# Shield_2_No_Ardy.net
KiCad netlist of a schematic drawn in EAGLE
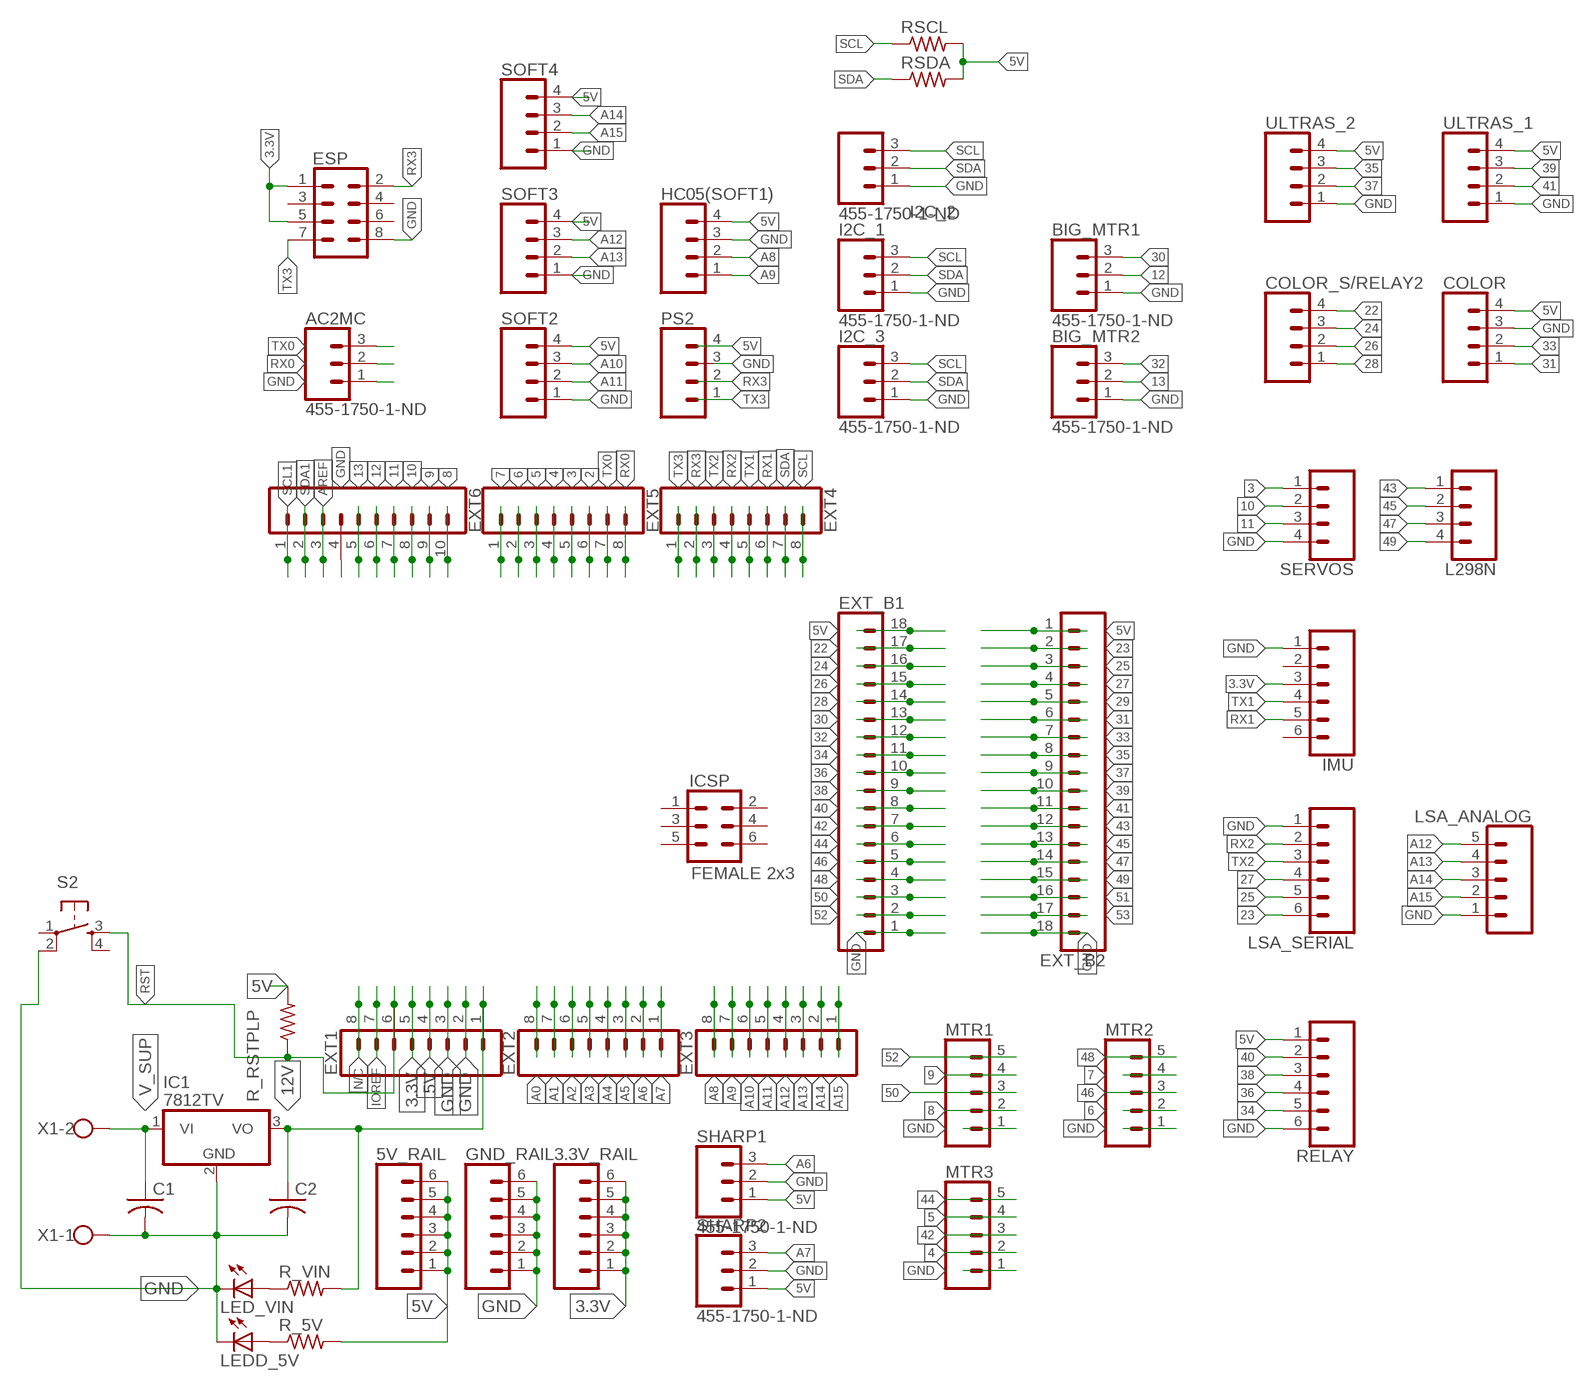
[diagram p0: schematic, sheet 1]

(export (version "E")
  (design (tool "Eeschema 10.0.6"))
  (components
    (comp (ref "3.3V_RAIL")
      (value "CONN_06SILK_FEMALE_PTH")
      (footprint "eagle-import:1X06")
      (libsource (lib "eagle-import") (part "CONN_06SILK_FEMALE_PTH"))
    )
    (comp (ref "5V_RAIL")
      (value "CONN_06SILK_FEMALE_PTH")
      (footprint "eagle-import:1X06")
      (libsource (lib "eagle-import") (part "CONN_06SILK_FEMALE_PTH"))
    )
    (comp (ref "AC2MC")
      (value "455-1750-1-ND")
      (footprint "eagle-import:1X03")
      (libsource (lib "eagle-import") (part "CONN_03"))
    )
    (comp (ref "BIG_MTR1")
      (value "455-1750-1-ND")
      (footprint "eagle-import:1X03")
      (libsource (lib "eagle-import") (part "CONN_03"))
    )
    (comp (ref "BIG_MTR2")
      (value "455-1750-1-ND")
      (footprint "eagle-import:1X03")
      (libsource (lib "eagle-import") (part "CONN_03"))
    )
    (comp (ref "C1")
      (value "C-US025-024X044")
      (footprint "eagle-import:C025-024X044")
      (libsource (lib "eagle-import") (part "C-US025-024X044"))
    )
    (comp (ref "C2")
      (value "C-US025-024X044")
      (footprint "eagle-import:C025-024X044")
      (libsource (lib "eagle-import") (part "C-US025-024X044"))
    )
    (comp (ref "COLOR")
      (value "CONN_04")
      (footprint "eagle-import:1X04")
      (libsource (lib "eagle-import") (part "CONN_04"))
    )
    (comp (ref "COLOR_S/RELAY2")
      (value "CONN_04")
      (footprint "eagle-import:1X04")
      (libsource (lib "eagle-import") (part "CONN_04"))
    )
    (comp (ref "ESP")
      (value "CONN_04X2")
      (footprint "eagle-import:2X4")
      (libsource (lib "eagle-import") (part "CONN_04X2"))
    )
    (comp (ref "EXT1")
      (value "CONN_08\"")
      (footprint "eagle-import:1X08")
      (libsource (lib "eagle-import") (part "CONN_08{dblquote}"))
    )
    (comp (ref "EXT2")
      (value "CONN_08\"")
      (footprint "eagle-import:1X08")
      (libsource (lib "eagle-import") (part "CONN_08{dblquote}"))
    )
    (comp (ref "EXT3")
      (value "CONN_08\"")
      (footprint "eagle-import:1X08")
      (libsource (lib "eagle-import") (part "CONN_08{dblquote}"))
    )
    (comp (ref "EXT4")
      (value "CONN_08\"")
      (footprint "eagle-import:1X08")
      (libsource (lib "eagle-import") (part "CONN_08{dblquote}"))
    )
    (comp (ref "EXT5")
      (value "CONN_08\"")
      (footprint "eagle-import:1X08")
      (libsource (lib "eagle-import") (part "CONN_08{dblquote}"))
    )
    (comp (ref "EXT6")
      (value "CONN_10\"")
      (footprint "eagle-import:1X10")
      (libsource (lib "eagle-import") (part "CONN_10{dblquote}"))
    )
    (comp (ref "EXT_B1")
      (value "CONN_18")
      (footprint "eagle-import:1X18_NO_SILK")
      (libsource (lib "eagle-import") (part "CONN_18"))
    )
    (comp (ref "EXT_B2")
      (value "CONN_18")
      (footprint "eagle-import:1X18_NO_SILK")
      (libsource (lib "eagle-import") (part "CONN_18"))
    )
    (comp (ref "GND_RAIL")
      (value "CONN_06SILK_FEMALE_PTH")
      (footprint "eagle-import:1X06")
      (libsource (lib "eagle-import") (part "CONN_06SILK_FEMALE_PTH"))
    )
    (comp (ref "HC05(SOFT1)")
      (value "CONN_04")
      (footprint "eagle-import:1X04")
      (libsource (lib "eagle-import") (part "CONN_04"))
    )
    (comp (ref "I2C_1")
      (value "455-1750-1-ND")
      (footprint "eagle-import:1X03")
      (libsource (lib "eagle-import") (part "CONN_03"))
    )
    (comp (ref "I2C_2")
      (value "455-1750-1-ND")
      (footprint "eagle-import:1X03")
      (libsource (lib "eagle-import") (part "CONN_03"))
    )
    (comp (ref "I2C_3")
      (value "455-1750-1-ND")
      (footprint "eagle-import:1X03")
      (libsource (lib "eagle-import") (part "CONN_03"))
    )
    (comp (ref "IC1")
      (value "7812TV")
      (footprint "eagle-import:TO220V")
      (libsource (lib "eagle-import") (part "78TV12"))
    )
    (comp (ref "ICSP")
      (value "FEMALE 2x3")
      (footprint "eagle-import:2X3")
      (libsource (lib "eagle-import") (part "CONN_03X2FEMALE"))
    )
    (comp (ref "IMU")
      (value "CONN_06SILK_FEMALE_PTH")
      (footprint "eagle-import:1X06")
      (libsource (lib "eagle-import") (part "CONN_06SILK_FEMALE_PTH"))
    )
    (comp (ref "L298N")
      (value "CONN_04")
      (footprint "eagle-import:1X04")
      (libsource (lib "eagle-import") (part "CONN_04"))
    )
    (comp (ref "LEDD_5V")
      (value "LED5MM")
      (footprint "eagle-import:LED5MM")
      (libsource (lib "eagle-import") (part "LED5MM"))
    )
    (comp (ref "LED_VIN")
      (value "LED5MM")
      (footprint "eagle-import:LED5MM")
      (libsource (lib "eagle-import") (part "LED5MM"))
    )
    (comp (ref "LSA_ANALOG")
      (value "CONN_05")
      (footprint "eagle-import:1X05")
      (libsource (lib "eagle-import") (part "CONN_05"))
    )
    (comp (ref "LSA_SERIAL")
      (value "CONN_06SILK_FEMALE_PTH")
      (footprint "eagle-import:1X06")
      (libsource (lib "eagle-import") (part "CONN_06SILK_FEMALE_PTH"))
    )
    (comp (ref "MTR1")
      (value "CONN_05")
      (footprint "eagle-import:1X05")
      (libsource (lib "eagle-import") (part "CONN_05"))
    )
    (comp (ref "MTR2")
      (value "CONN_05")
      (footprint "eagle-import:1X05")
      (libsource (lib "eagle-import") (part "CONN_05"))
    )
    (comp (ref "MTR3")
      (value "CONN_05")
      (footprint "eagle-import:1X05")
      (libsource (lib "eagle-import") (part "CONN_05"))
    )
    (comp (ref "PS2")
      (value "CONN_04")
      (footprint "eagle-import:1X04")
      (libsource (lib "eagle-import") (part "CONN_04"))
    )
    (comp (ref "RELAY")
      (value "CONN_06SILK_FEMALE_PTH")
      (footprint "eagle-import:1X06")
      (libsource (lib "eagle-import") (part "CONN_06SILK_FEMALE_PTH"))
    )
    (comp (ref "RSCL")
      (value "R-US_0204/7")
      (footprint "eagle-import:0204_7")
      (libsource (lib "eagle-import") (part "R-US_0204/7"))
    )
    (comp (ref "RSDA")
      (value "R-US_0204/7")
      (footprint "eagle-import:0204_7")
      (libsource (lib "eagle-import") (part "R-US_0204/7"))
    )
    (comp (ref "R_5V")
      (value "R-US_0204/7")
      (footprint "eagle-import:0204_7")
      (libsource (lib "eagle-import") (part "R-US_0204/7"))
    )
    (comp (ref "R_RSTPLP")
      (value "R-US_0204/7")
      (footprint "eagle-import:0204_7")
      (libsource (lib "eagle-import") (part "R-US_0204/7"))
    )
    (comp (ref "R_VIN")
      (value "R-US_0204/7")
      (footprint "eagle-import:0204_7")
      (libsource (lib "eagle-import") (part "R-US_0204/7"))
    )
    (comp (ref "S2")
      (value "TAC_SWITCHPTH")
      (footprint "eagle-import:TACTILE-PTH")
      (libsource (lib "eagle-import") (part "TAC_SWITCHPTH"))
    )
    (comp (ref "SERVOS")
      (value "CONN_04")
      (footprint "eagle-import:1X04")
      (libsource (lib "eagle-import") (part "CONN_04"))
    )
    (comp (ref "SHARP1")
      (value "455-1750-1-ND")
      (footprint "eagle-import:1X03")
      (libsource (lib "eagle-import") (part "CONN_03"))
    )
    (comp (ref "SHARP2")
      (value "455-1750-1-ND")
      (footprint "eagle-import:1X03")
      (libsource (lib "eagle-import") (part "CONN_03"))
    )
    (comp (ref "SOFT2")
      (value "CONN_04")
      (footprint "eagle-import:1X04")
      (libsource (lib "eagle-import") (part "CONN_04"))
    )
    (comp (ref "SOFT3")
      (value "CONN_04")
      (footprint "eagle-import:1X04")
      (libsource (lib "eagle-import") (part "CONN_04"))
    )
    (comp (ref "SOFT4")
      (value "CONN_04")
      (footprint "eagle-import:1X04")
      (libsource (lib "eagle-import") (part "CONN_04"))
    )
    (comp (ref "ULTRAS_1")
      (value "CONN_04")
      (footprint "eagle-import:1X04")
      (libsource (lib "eagle-import") (part "CONN_04"))
    )
    (comp (ref "ULTRAS_2")
      (value "CONN_04")
      (footprint "eagle-import:1X04")
      (libsource (lib "eagle-import") (part "CONN_04"))
    )
    (comp (ref "X1")
      (value "W237-102")
      (footprint "eagle-import:W237-102")
      (fields (field (name "MPN") "237-102"))
      (libsource (lib "eagle-import") (part "W237-102"))
    )
  )
  (nets
    (net (code "1") (name "2") (class "Default")
      (node (ref "EXT5") (pin "6") (pinfunction "6_6") (pintype "passive"))
    )
    (net (code "2") (name "3") (class "Default")
      (node (ref "EXT5") (pin "5") (pinfunction "5_5") (pintype "passive"))
      (node (ref "SERVOS") (pin "1") (pinfunction "1_1") (pintype "passive"))
    )
    (net (code "3") (name "3.3V") (class "Default")
      (node (ref "3.3V_RAIL") (pin "1") (pinfunction "1_1") (pintype "passive"))
      (node (ref "3.3V_RAIL") (pin "2") (pinfunction "2_2") (pintype "passive"))
      (node (ref "3.3V_RAIL") (pin "3") (pinfunction "3_3") (pintype "passive"))
      (node (ref "3.3V_RAIL") (pin "4") (pinfunction "4_4") (pintype "passive"))
      (node (ref "3.3V_RAIL") (pin "5") (pinfunction "5_5") (pintype "passive"))
      (node (ref "3.3V_RAIL") (pin "6") (pinfunction "6_6") (pintype "passive"))
      (node (ref "ESP") (pin "1") (pinfunction "1_1") (pintype "passive"))
      (node (ref "ESP") (pin "5") (pinfunction "5_5") (pintype "passive"))
      (node (ref "EXT1") (pin "5") (pinfunction "5_5") (pintype "passive"))
      (node (ref "IMU") (pin "3") (pinfunction "3_3") (pintype "passive"))
    )
    (net (code "4") (name "4") (class "Default")
      (node (ref "EXT5") (pin "4") (pinfunction "4_4") (pintype "passive"))
      (node (ref "MTR3") (pin "2") (pinfunction "2_2") (pintype "passive"))
    )
    (net (code "5") (name "5") (class "Default")
      (node (ref "EXT5") (pin "3") (pinfunction "3_3") (pintype "passive"))
      (node (ref "MTR3") (pin "4") (pinfunction "4_4") (pintype "passive"))
    )
    (net (code "6") (name "5V") (class "Default")
      (node (ref "5V_RAIL") (pin "1") (pinfunction "1_1") (pintype "passive"))
      (node (ref "5V_RAIL") (pin "2") (pinfunction "2_2") (pintype "passive"))
      (node (ref "5V_RAIL") (pin "3") (pinfunction "3_3") (pintype "passive"))
      (node (ref "5V_RAIL") (pin "4") (pinfunction "4_4") (pintype "passive"))
      (node (ref "5V_RAIL") (pin "5") (pinfunction "5_5") (pintype "passive"))
      (node (ref "5V_RAIL") (pin "6") (pinfunction "6_6") (pintype "passive"))
      (node (ref "COLOR") (pin "4") (pinfunction "4_4") (pintype "passive"))
      (node (ref "EXT1") (pin "4") (pinfunction "4_4") (pintype "passive"))
      (node (ref "EXT_B1") (pin "18") (pinfunction "18_18") (pintype "passive"))
      (node (ref "EXT_B2") (pin "1") (pinfunction "1_1") (pintype "passive"))
      (node (ref "HC05(SOFT1)") (pin "4") (pinfunction "4_4") (pintype "passive"))
      (node (ref "PS2") (pin "4") (pinfunction "4_4") (pintype "passive"))
      (node (ref "RELAY") (pin "1") (pinfunction "1_1") (pintype "passive"))
      (node (ref "RSCL") (pin "2") (pinfunction "2_2") (pintype "passive"))
      (node (ref "RSDA") (pin "2") (pinfunction "2_2") (pintype "passive"))
      (node (ref "R_5V") (pin "2") (pinfunction "2_2") (pintype "passive"))
      (node (ref "R_RSTPLP") (pin "2") (pinfunction "2_2") (pintype "passive"))
      (node (ref "SHARP1") (pin "1") (pinfunction "1_1") (pintype "passive"))
      (node (ref "SHARP2") (pin "1") (pinfunction "1_1") (pintype "passive"))
      (node (ref "SOFT2") (pin "4") (pinfunction "4_4") (pintype "passive"))
      (node (ref "SOFT3") (pin "4") (pinfunction "4_4") (pintype "passive"))
      (node (ref "SOFT4") (pin "4") (pinfunction "4_4") (pintype "passive"))
      (node (ref "ULTRAS_1") (pin "4") (pinfunction "4_4") (pintype "passive"))
      (node (ref "ULTRAS_2") (pin "4") (pinfunction "4_4") (pintype "passive"))
    )
    (net (code "7") (name "6") (class "Default")
      (node (ref "EXT5") (pin "2") (pinfunction "2_2") (pintype "passive"))
      (node (ref "MTR2") (pin "2") (pinfunction "2_2") (pintype "passive"))
    )
    (net (code "8") (name "7") (class "Default")
      (node (ref "EXT5") (pin "1") (pinfunction "1_1") (pintype "passive"))
      (node (ref "MTR2") (pin "4") (pinfunction "4_4") (pintype "passive"))
    )
    (net (code "9") (name "8") (class "Default")
      (node (ref "EXT6") (pin "10") (pinfunction "10_10") (pintype "passive"))
      (node (ref "MTR1") (pin "2") (pinfunction "2_2") (pintype "passive"))
    )
    (net (code "10") (name "9") (class "Default")
      (node (ref "EXT6") (pin "9") (pinfunction "9_9") (pintype "passive"))
      (node (ref "MTR1") (pin "4") (pinfunction "4_4") (pintype "passive"))
    )
    (net (code "11") (name "10") (class "Default")
      (node (ref "EXT6") (pin "8") (pinfunction "8_8") (pintype "passive"))
      (node (ref "SERVOS") (pin "2") (pinfunction "2_2") (pintype "passive"))
    )
    (net (code "12") (name "11") (class "Default")
      (node (ref "EXT6") (pin "7") (pinfunction "7_7") (pintype "passive"))
      (node (ref "SERVOS") (pin "3") (pinfunction "3_3") (pintype "passive"))
    )
    (net (code "13") (name "12") (class "Default")
      (node (ref "BIG_MTR1") (pin "2") (pinfunction "2_2") (pintype "passive"))
      (node (ref "EXT6") (pin "6") (pinfunction "6_6") (pintype "passive"))
    )
    (net (code "14") (name "12V") (class "Default")
      (node (ref "C2") (pin "1") (pinfunction "1_1") (pintype "passive"))
      (node (ref "EXT1") (pin "1") (pinfunction "1_1") (pintype "passive"))
      (node (ref "IC1") (pin "3") (pinfunction "VO_3") (pintype "passive"))
      (node (ref "R_VIN") (pin "2") (pinfunction "2_2") (pintype "passive"))
    )
    (net (code "15") (name "13") (class "Default")
      (node (ref "BIG_MTR2") (pin "2") (pinfunction "2_2") (pintype "passive"))
      (node (ref "EXT6") (pin "5") (pinfunction "5_5") (pintype "passive"))
    )
    (net (code "16") (name "22") (class "Default")
      (node (ref "COLOR_S/RELAY2") (pin "4") (pinfunction "4_4") (pintype "passive"))
      (node (ref "EXT_B1") (pin "17") (pinfunction "17_17") (pintype "passive"))
    )
    (net (code "17") (name "23") (class "Default")
      (node (ref "EXT_B2") (pin "2") (pinfunction "2_2") (pintype "passive"))
      (node (ref "LSA_SERIAL") (pin "6") (pinfunction "6_6") (pintype "passive"))
    )
    (net (code "18") (name "24") (class "Default")
      (node (ref "COLOR_S/RELAY2") (pin "3") (pinfunction "3_3") (pintype "passive"))
      (node (ref "EXT_B1") (pin "16") (pinfunction "16_16") (pintype "passive"))
    )
    (net (code "19") (name "25") (class "Default")
      (node (ref "EXT_B2") (pin "3") (pinfunction "3_3") (pintype "passive"))
      (node (ref "LSA_SERIAL") (pin "5") (pinfunction "5_5") (pintype "passive"))
    )
    (net (code "20") (name "26") (class "Default")
      (node (ref "COLOR_S/RELAY2") (pin "2") (pinfunction "2_2") (pintype "passive"))
      (node (ref "EXT_B1") (pin "15") (pinfunction "15_15") (pintype "passive"))
    )
    (net (code "21") (name "27") (class "Default")
      (node (ref "EXT_B2") (pin "4") (pinfunction "4_4") (pintype "passive"))
      (node (ref "LSA_SERIAL") (pin "4") (pinfunction "4_4") (pintype "passive"))
    )
    (net (code "22") (name "28") (class "Default")
      (node (ref "COLOR_S/RELAY2") (pin "1") (pinfunction "1_1") (pintype "passive"))
      (node (ref "EXT_B1") (pin "14") (pinfunction "14_14") (pintype "passive"))
    )
    (net (code "23") (name "29") (class "Default")
      (node (ref "EXT_B2") (pin "5") (pinfunction "5_5") (pintype "passive"))
    )
    (net (code "24") (name "30") (class "Default")
      (node (ref "BIG_MTR1") (pin "3") (pinfunction "3_3") (pintype "passive"))
      (node (ref "EXT_B1") (pin "13") (pinfunction "13_13") (pintype "passive"))
    )
    (net (code "25") (name "31") (class "Default")
      (node (ref "COLOR") (pin "1") (pinfunction "1_1") (pintype "passive"))
      (node (ref "EXT_B2") (pin "6") (pinfunction "6_6") (pintype "passive"))
    )
    (net (code "26") (name "32") (class "Default")
      (node (ref "BIG_MTR2") (pin "3") (pinfunction "3_3") (pintype "passive"))
      (node (ref "EXT_B1") (pin "12") (pinfunction "12_12") (pintype "passive"))
    )
    (net (code "27") (name "33") (class "Default")
      (node (ref "COLOR") (pin "2") (pinfunction "2_2") (pintype "passive"))
      (node (ref "EXT_B2") (pin "7") (pinfunction "7_7") (pintype "passive"))
    )
    (net (code "28") (name "34") (class "Default")
      (node (ref "EXT_B1") (pin "11") (pinfunction "11_11") (pintype "passive"))
      (node (ref "RELAY") (pin "5") (pinfunction "5_5") (pintype "passive"))
    )
    (net (code "29") (name "35") (class "Default")
      (node (ref "EXT_B2") (pin "8") (pinfunction "8_8") (pintype "passive"))
      (node (ref "ULTRAS_2") (pin "3") (pinfunction "3_3") (pintype "passive"))
    )
    (net (code "30") (name "36") (class "Default")
      (node (ref "EXT_B1") (pin "10") (pinfunction "10_10") (pintype "passive"))
      (node (ref "RELAY") (pin "4") (pinfunction "4_4") (pintype "passive"))
    )
    (net (code "31") (name "37") (class "Default")
      (node (ref "EXT_B2") (pin "9") (pinfunction "9_9") (pintype "passive"))
      (node (ref "ULTRAS_2") (pin "2") (pinfunction "2_2") (pintype "passive"))
    )
    (net (code "32") (name "38") (class "Default")
      (node (ref "EXT_B1") (pin "9") (pinfunction "9_9") (pintype "passive"))
      (node (ref "RELAY") (pin "3") (pinfunction "3_3") (pintype "passive"))
    )
    (net (code "33") (name "39") (class "Default")
      (node (ref "EXT_B2") (pin "10") (pinfunction "10_10") (pintype "passive"))
      (node (ref "ULTRAS_1") (pin "3") (pinfunction "3_3") (pintype "passive"))
    )
    (net (code "34") (name "40") (class "Default")
      (node (ref "EXT_B1") (pin "8") (pinfunction "8_8") (pintype "passive"))
      (node (ref "RELAY") (pin "2") (pinfunction "2_2") (pintype "passive"))
    )
    (net (code "35") (name "41") (class "Default")
      (node (ref "EXT_B2") (pin "11") (pinfunction "11_11") (pintype "passive"))
      (node (ref "ULTRAS_1") (pin "2") (pinfunction "2_2") (pintype "passive"))
    )
    (net (code "36") (name "42") (class "Default")
      (node (ref "EXT_B1") (pin "7") (pinfunction "7_7") (pintype "passive"))
      (node (ref "MTR3") (pin "3") (pinfunction "3_3") (pintype "passive"))
    )
    (net (code "37") (name "43") (class "Default")
      (node (ref "EXT_B2") (pin "12") (pinfunction "12_12") (pintype "passive"))
      (node (ref "L298N") (pin "1") (pinfunction "1_1") (pintype "passive"))
    )
    (net (code "38") (name "44") (class "Default")
      (node (ref "EXT_B1") (pin "6") (pinfunction "6_6") (pintype "passive"))
      (node (ref "MTR3") (pin "5") (pinfunction "5_5") (pintype "passive"))
    )
    (net (code "39") (name "45") (class "Default")
      (node (ref "EXT_B2") (pin "13") (pinfunction "13_13") (pintype "passive"))
      (node (ref "L298N") (pin "2") (pinfunction "2_2") (pintype "passive"))
    )
    (net (code "40") (name "46") (class "Default")
      (node (ref "EXT_B1") (pin "5") (pinfunction "5_5") (pintype "passive"))
      (node (ref "MTR2") (pin "3") (pinfunction "3_3") (pintype "passive"))
    )
    (net (code "41") (name "47") (class "Default")
      (node (ref "EXT_B2") (pin "14") (pinfunction "14_14") (pintype "passive"))
      (node (ref "L298N") (pin "3") (pinfunction "3_3") (pintype "passive"))
    )
    (net (code "42") (name "48") (class "Default")
      (node (ref "EXT_B1") (pin "4") (pinfunction "4_4") (pintype "passive"))
      (node (ref "MTR2") (pin "5") (pinfunction "5_5") (pintype "passive"))
    )
    (net (code "43") (name "49") (class "Default")
      (node (ref "EXT_B2") (pin "15") (pinfunction "15_15") (pintype "passive"))
      (node (ref "L298N") (pin "4") (pinfunction "4_4") (pintype "passive"))
    )
    (net (code "44") (name "50") (class "Default")
      (node (ref "EXT_B1") (pin "3") (pinfunction "3_3") (pintype "passive"))
      (node (ref "MTR1") (pin "3") (pinfunction "3_3") (pintype "passive"))
    )
    (net (code "45") (name "51") (class "Default")
      (node (ref "EXT_B2") (pin "16") (pinfunction "16_16") (pintype "passive"))
    )
    (net (code "46") (name "52") (class "Default")
      (node (ref "EXT_B1") (pin "2") (pinfunction "2_2") (pintype "passive"))
      (node (ref "MTR1") (pin "5") (pinfunction "5_5") (pintype "passive"))
    )
    (net (code "47") (name "53") (class "Default")
      (node (ref "EXT_B2") (pin "17") (pinfunction "17_17") (pintype "passive"))
    )
    (net (code "48") (name "A0") (class "Default")
      (node (ref "EXT2") (pin "8") (pinfunction "8_8") (pintype "passive"))
    )
    (net (code "49") (name "A1") (class "Default")
      (node (ref "EXT2") (pin "7") (pinfunction "7_7") (pintype "passive"))
    )
    (net (code "50") (name "A2") (class "Default")
      (node (ref "EXT2") (pin "6") (pinfunction "6_6") (pintype "passive"))
    )
    (net (code "51") (name "A3") (class "Default")
      (node (ref "EXT2") (pin "5") (pinfunction "5_5") (pintype "passive"))
    )
    (net (code "52") (name "A4") (class "Default")
      (node (ref "EXT2") (pin "4") (pinfunction "4_4") (pintype "passive"))
    )
    (net (code "53") (name "A5") (class "Default")
      (node (ref "EXT2") (pin "3") (pinfunction "3_3") (pintype "passive"))
    )
    (net (code "54") (name "A6") (class "Default")
      (node (ref "EXT2") (pin "2") (pinfunction "2_2") (pintype "passive"))
      (node (ref "SHARP1") (pin "3") (pinfunction "3_3") (pintype "passive"))
    )
    (net (code "55") (name "A7") (class "Default")
      (node (ref "EXT2") (pin "1") (pinfunction "1_1") (pintype "passive"))
      (node (ref "SHARP2") (pin "3") (pinfunction "3_3") (pintype "passive"))
    )
    (net (code "56") (name "A8") (class "Default")
      (node (ref "EXT3") (pin "8") (pinfunction "8_8") (pintype "passive"))
      (node (ref "HC05(SOFT1)") (pin "2") (pinfunction "2_2") (pintype "passive"))
    )
    (net (code "57") (name "A9") (class "Default")
      (node (ref "EXT3") (pin "7") (pinfunction "7_7") (pintype "passive"))
      (node (ref "HC05(SOFT1)") (pin "1") (pinfunction "1_1") (pintype "passive"))
    )
    (net (code "58") (name "A10") (class "Default")
      (node (ref "EXT3") (pin "6") (pinfunction "6_6") (pintype "passive"))
      (node (ref "SOFT2") (pin "3") (pinfunction "3_3") (pintype "passive"))
    )
    (net (code "59") (name "A11") (class "Default")
      (node (ref "EXT3") (pin "5") (pinfunction "5_5") (pintype "passive"))
      (node (ref "SOFT2") (pin "2") (pinfunction "2_2") (pintype "passive"))
    )
    (net (code "60") (name "A12") (class "Default")
      (node (ref "EXT3") (pin "4") (pinfunction "4_4") (pintype "passive"))
      (node (ref "LSA_ANALOG") (pin "5") (pinfunction "5_5") (pintype "passive"))
      (node (ref "SOFT3") (pin "3") (pinfunction "3_3") (pintype "passive"))
    )
    (net (code "61") (name "A13") (class "Default")
      (node (ref "EXT3") (pin "3") (pinfunction "3_3") (pintype "passive"))
      (node (ref "LSA_ANALOG") (pin "4") (pinfunction "4_4") (pintype "passive"))
      (node (ref "SOFT3") (pin "2") (pinfunction "2_2") (pintype "passive"))
    )
    (net (code "62") (name "A14") (class "Default")
      (node (ref "EXT3") (pin "2") (pinfunction "2_2") (pintype "passive"))
      (node (ref "LSA_ANALOG") (pin "3") (pinfunction "3_3") (pintype "passive"))
      (node (ref "SOFT4") (pin "3") (pinfunction "3_3") (pintype "passive"))
    )
    (net (code "63") (name "A15") (class "Default")
      (node (ref "EXT3") (pin "1") (pinfunction "1_1") (pintype "passive"))
      (node (ref "LSA_ANALOG") (pin "2") (pinfunction "2_2") (pintype "passive"))
      (node (ref "SOFT4") (pin "2") (pinfunction "2_2") (pintype "passive"))
    )
    (net (code "64") (name "AREF") (class "Default")
      (node (ref "EXT6") (pin "3") (pinfunction "3_3") (pintype "passive"))
    )
    (net (code "65") (name "GND") (class "Default")
      (node (ref "AC2MC") (pin "1") (pinfunction "1_1") (pintype "passive"))
      (node (ref "BIG_MTR1") (pin "1") (pinfunction "1_1") (pintype "passive"))
      (node (ref "BIG_MTR2") (pin "1") (pinfunction "1_1") (pintype "passive"))
      (node (ref "C1") (pin "2") (pinfunction "2_2") (pintype "passive"))
      (node (ref "C2") (pin "2") (pinfunction "2_2") (pintype "passive"))
      (node (ref "COLOR") (pin "3") (pinfunction "3_3") (pintype "passive"))
      (node (ref "ESP") (pin "8") (pinfunction "8_8") (pintype "passive"))
      (node (ref "EXT1") (pin "2") (pinfunction "2_2") (pintype "passive"))
      (node (ref "EXT1") (pin "3") (pinfunction "3_3") (pintype "passive"))
      (node (ref "EXT6") (pin "4") (pinfunction "4_4") (pintype "passive"))
      (node (ref "EXT_B1") (pin "1") (pinfunction "1_1") (pintype "passive"))
      (node (ref "EXT_B2") (pin "18") (pinfunction "18_18") (pintype "passive"))
      (node (ref "GND_RAIL") (pin "1") (pinfunction "1_1") (pintype "passive"))
      (node (ref "GND_RAIL") (pin "2") (pinfunction "2_2") (pintype "passive"))
      (node (ref "GND_RAIL") (pin "3") (pinfunction "3_3") (pintype "passive"))
      (node (ref "GND_RAIL") (pin "4") (pinfunction "4_4") (pintype "passive"))
      (node (ref "GND_RAIL") (pin "5") (pinfunction "5_5") (pintype "passive"))
      (node (ref "GND_RAIL") (pin "6") (pinfunction "6_6") (pintype "passive"))
      (node (ref "HC05(SOFT1)") (pin "3") (pinfunction "3_3") (pintype "passive"))
      (node (ref "I2C_1") (pin "1") (pinfunction "1_1") (pintype "passive"))
      (node (ref "I2C_2") (pin "1") (pinfunction "1_1") (pintype "passive"))
      (node (ref "I2C_3") (pin "1") (pinfunction "1_1") (pintype "passive"))
      (node (ref "IC1") (pin "2") (pinfunction "GND_2") (pintype "passive"))
      (node (ref "IMU") (pin "1") (pinfunction "1_1") (pintype "passive"))
      (node (ref "LEDD_5V") (pin "K") (pinfunction "C_K") (pintype "passive"))
      (node (ref "LED_VIN") (pin "K") (pinfunction "C_K") (pintype "passive"))
      (node (ref "LSA_ANALOG") (pin "1") (pinfunction "1_1") (pintype "passive"))
      (node (ref "LSA_SERIAL") (pin "1") (pinfunction "1_1") (pintype "passive"))
      (node (ref "MTR1") (pin "1") (pinfunction "1_1") (pintype "passive"))
      (node (ref "MTR2") (pin "1") (pinfunction "1_1") (pintype "passive"))
      (node (ref "MTR3") (pin "1") (pinfunction "1_1") (pintype "passive"))
      (node (ref "PS2") (pin "3") (pinfunction "3_3") (pintype "passive"))
      (node (ref "RELAY") (pin "6") (pinfunction "6_6") (pintype "passive"))
      (node (ref "S2") (pin "2") (pinfunction "2_2") (pintype "passive"))
      (node (ref "SERVOS") (pin "4") (pinfunction "4_4") (pintype "passive"))
      (node (ref "SHARP1") (pin "2") (pinfunction "2_2") (pintype "passive"))
      (node (ref "SHARP2") (pin "2") (pinfunction "2_2") (pintype "passive"))
      (node (ref "SOFT2") (pin "1") (pinfunction "1_1") (pintype "passive"))
      (node (ref "SOFT3") (pin "1") (pinfunction "1_1") (pintype "passive"))
      (node (ref "SOFT4") (pin "1") (pinfunction "1_1") (pintype "passive"))
      (node (ref "ULTRAS_1") (pin "1") (pinfunction "1_1") (pintype "passive"))
      (node (ref "ULTRAS_2") (pin "1") (pinfunction "1_1") (pintype "passive"))
      (node (ref "X1") (pin "1") (pinfunction "KL_1") (pintype "passive"))
    )
    (net (code "66") (name "IOREF") (class "Default")
      (node (ref "EXT1") (pin "7") (pinfunction "7_7") (pintype "passive"))
    )
    (net (code "67") (name "Net-(LEDD_5V-PadA)") (class "Default")
      (node (ref "LEDD_5V") (pin "A") (pinfunction "A_A") (pintype "passive"))
      (node (ref "R_5V") (pin "1") (pinfunction "1_1") (pintype "passive"))
    )
    (net (code "68") (name "Net-(LED_VIN-PadA)") (class "Default")
      (node (ref "LED_VIN") (pin "A") (pinfunction "A_A") (pintype "passive"))
      (node (ref "R_VIN") (pin "1") (pinfunction "1_1") (pintype "passive"))
    )
    (net (code "69") (name "N{slash}C") (class "Default")
      (node (ref "EXT1") (pin "8") (pinfunction "8_8") (pintype "passive"))
    )
    (net (code "70") (name "RST") (class "Default")
      (node (ref "EXT1") (pin "6") (pinfunction "6_6") (pintype "passive"))
      (node (ref "R_RSTPLP") (pin "1") (pinfunction "1_1") (pintype "passive"))
      (node (ref "S2") (pin "3") (pinfunction "3_3") (pintype "passive"))
    )
    (net (code "71") (name "RX0") (class "Default")
      (node (ref "AC2MC") (pin "2") (pinfunction "2_2") (pintype "passive"))
      (node (ref "EXT5") (pin "8") (pinfunction "8_8") (pintype "passive"))
    )
    (net (code "72") (name "RX1") (class "Default")
      (node (ref "EXT4") (pin "6") (pinfunction "6_6") (pintype "passive"))
      (node (ref "IMU") (pin "5") (pinfunction "5_5") (pintype "passive"))
    )
    (net (code "73") (name "RX2") (class "Default")
      (node (ref "EXT4") (pin "4") (pinfunction "4_4") (pintype "passive"))
      (node (ref "LSA_SERIAL") (pin "2") (pinfunction "2_2") (pintype "passive"))
    )
    (net (code "74") (name "RX3") (class "Default")
      (node (ref "ESP") (pin "2") (pinfunction "2_2") (pintype "passive"))
      (node (ref "EXT4") (pin "2") (pinfunction "2_2") (pintype "passive"))
      (node (ref "PS2") (pin "2") (pinfunction "2_2") (pintype "passive"))
    )
    (net (code "75") (name "SCL") (class "Default")
      (node (ref "EXT4") (pin "8") (pinfunction "8_8") (pintype "passive"))
      (node (ref "I2C_1") (pin "3") (pinfunction "3_3") (pintype "passive"))
      (node (ref "I2C_2") (pin "3") (pinfunction "3_3") (pintype "passive"))
      (node (ref "I2C_3") (pin "3") (pinfunction "3_3") (pintype "passive"))
      (node (ref "RSCL") (pin "1") (pinfunction "1_1") (pintype "passive"))
    )
    (net (code "76") (name "SCL1") (class "Default")
      (node (ref "EXT6") (pin "1") (pinfunction "1_1") (pintype "passive"))
    )
    (net (code "77") (name "SDA") (class "Default")
      (node (ref "EXT4") (pin "7") (pinfunction "7_7") (pintype "passive"))
      (node (ref "I2C_1") (pin "2") (pinfunction "2_2") (pintype "passive"))
      (node (ref "I2C_2") (pin "2") (pinfunction "2_2") (pintype "passive"))
      (node (ref "I2C_3") (pin "2") (pinfunction "2_2") (pintype "passive"))
      (node (ref "RSDA") (pin "1") (pinfunction "1_1") (pintype "passive"))
    )
    (net (code "78") (name "SDA1") (class "Default")
      (node (ref "EXT6") (pin "2") (pinfunction "2_2") (pintype "passive"))
    )
    (net (code "79") (name "TX0") (class "Default")
      (node (ref "AC2MC") (pin "3") (pinfunction "3_3") (pintype "passive"))
      (node (ref "EXT5") (pin "7") (pinfunction "7_7") (pintype "passive"))
    )
    (net (code "80") (name "TX1") (class "Default")
      (node (ref "EXT4") (pin "5") (pinfunction "5_5") (pintype "passive"))
      (node (ref "IMU") (pin "4") (pinfunction "4_4") (pintype "passive"))
    )
    (net (code "81") (name "TX2") (class "Default")
      (node (ref "EXT4") (pin "3") (pinfunction "3_3") (pintype "passive"))
      (node (ref "LSA_SERIAL") (pin "3") (pinfunction "3_3") (pintype "passive"))
    )
    (net (code "82") (name "TX3") (class "Default")
      (node (ref "ESP") (pin "7") (pinfunction "7_7") (pintype "passive"))
      (node (ref "EXT4") (pin "1") (pinfunction "1_1") (pintype "passive"))
      (node (ref "PS2") (pin "1") (pinfunction "1_1") (pintype "passive"))
    )
    (net (code "83") (name "V_SUP") (class "Default")
      (node (ref "C1") (pin "1") (pinfunction "1_1") (pintype "passive"))
      (node (ref "IC1") (pin "1") (pinfunction "VI_1") (pintype "input"))
      (node (ref "X1") (pin "2") (pinfunction "KL_2") (pintype "passive"))
    )
    (net (code "84") (name "unconnected-(ESP-Pad3)") (class "Default")
      (node (ref "ESP") (pin "3") (pinfunction "3_3") (pintype "passive"))
    )
    (net (code "85") (name "unconnected-(ESP-Pad4)") (class "Default")
      (node (ref "ESP") (pin "4") (pinfunction "4_4") (pintype "passive"))
    )
    (net (code "86") (name "unconnected-(ESP-Pad6)") (class "Default")
      (node (ref "ESP") (pin "6") (pinfunction "6_6") (pintype "passive"))
    )
    (net (code "87") (name "unconnected-(ICSP-Pad1)") (class "Default")
      (node (ref "ICSP") (pin "1") (pinfunction "1_1") (pintype "bidirectional"))
    )
    (net (code "88") (name "unconnected-(ICSP-Pad2)") (class "Default")
      (node (ref "ICSP") (pin "2") (pinfunction "2_2") (pintype "bidirectional"))
    )
    (net (code "89") (name "unconnected-(ICSP-Pad3)") (class "Default")
      (node (ref "ICSP") (pin "3") (pinfunction "3_3") (pintype "bidirectional"))
    )
    (net (code "90") (name "unconnected-(ICSP-Pad4)") (class "Default")
      (node (ref "ICSP") (pin "4") (pinfunction "4_4") (pintype "bidirectional"))
    )
    (net (code "91") (name "unconnected-(ICSP-Pad5)") (class "Default")
      (node (ref "ICSP") (pin "5") (pinfunction "5_5") (pintype "bidirectional"))
    )
    (net (code "92") (name "unconnected-(ICSP-Pad6)") (class "Default")
      (node (ref "ICSP") (pin "6") (pinfunction "6_6") (pintype "bidirectional"))
    )
    (net (code "93") (name "unconnected-(IMU-Pad2)") (class "Default")
      (node (ref "IMU") (pin "2") (pinfunction "2_2") (pintype "passive"))
    )
    (net (code "94") (name "unconnected-(IMU-Pad6)") (class "Default")
      (node (ref "IMU") (pin "6") (pinfunction "6_6") (pintype "passive"))
    )
    (net (code "95") (name "unconnected-(S2-Pad1)") (class "Default")
      (node (ref "S2") (pin "1") (pinfunction "1_1") (pintype "passive"))
    )
    (net (code "96") (name "unconnected-(S2-Pad4)") (class "Default")
      (node (ref "S2") (pin "4") (pinfunction "4_4") (pintype "passive"))
    )
  )
)
